# SSTuino_Evo.net
KiCad netlist of a schematic drawn in EAGLE
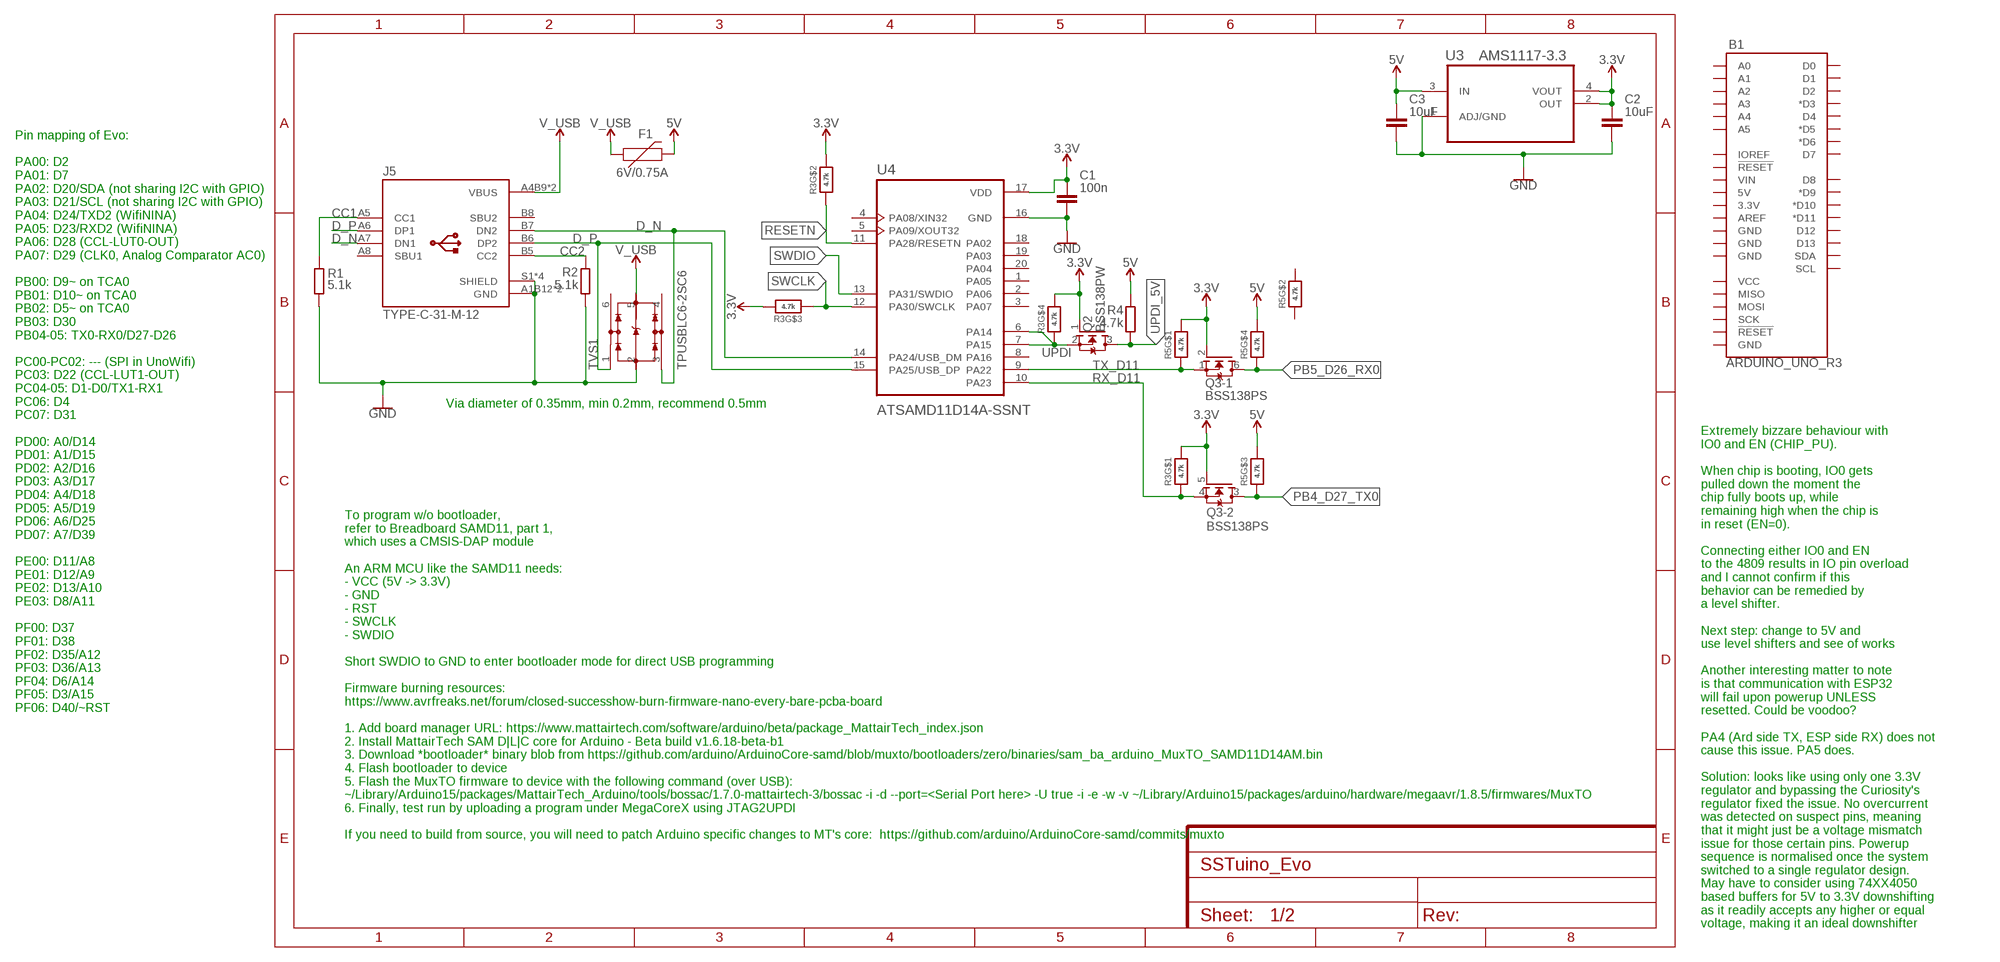
[diagram p0: schematic, sheet 1]
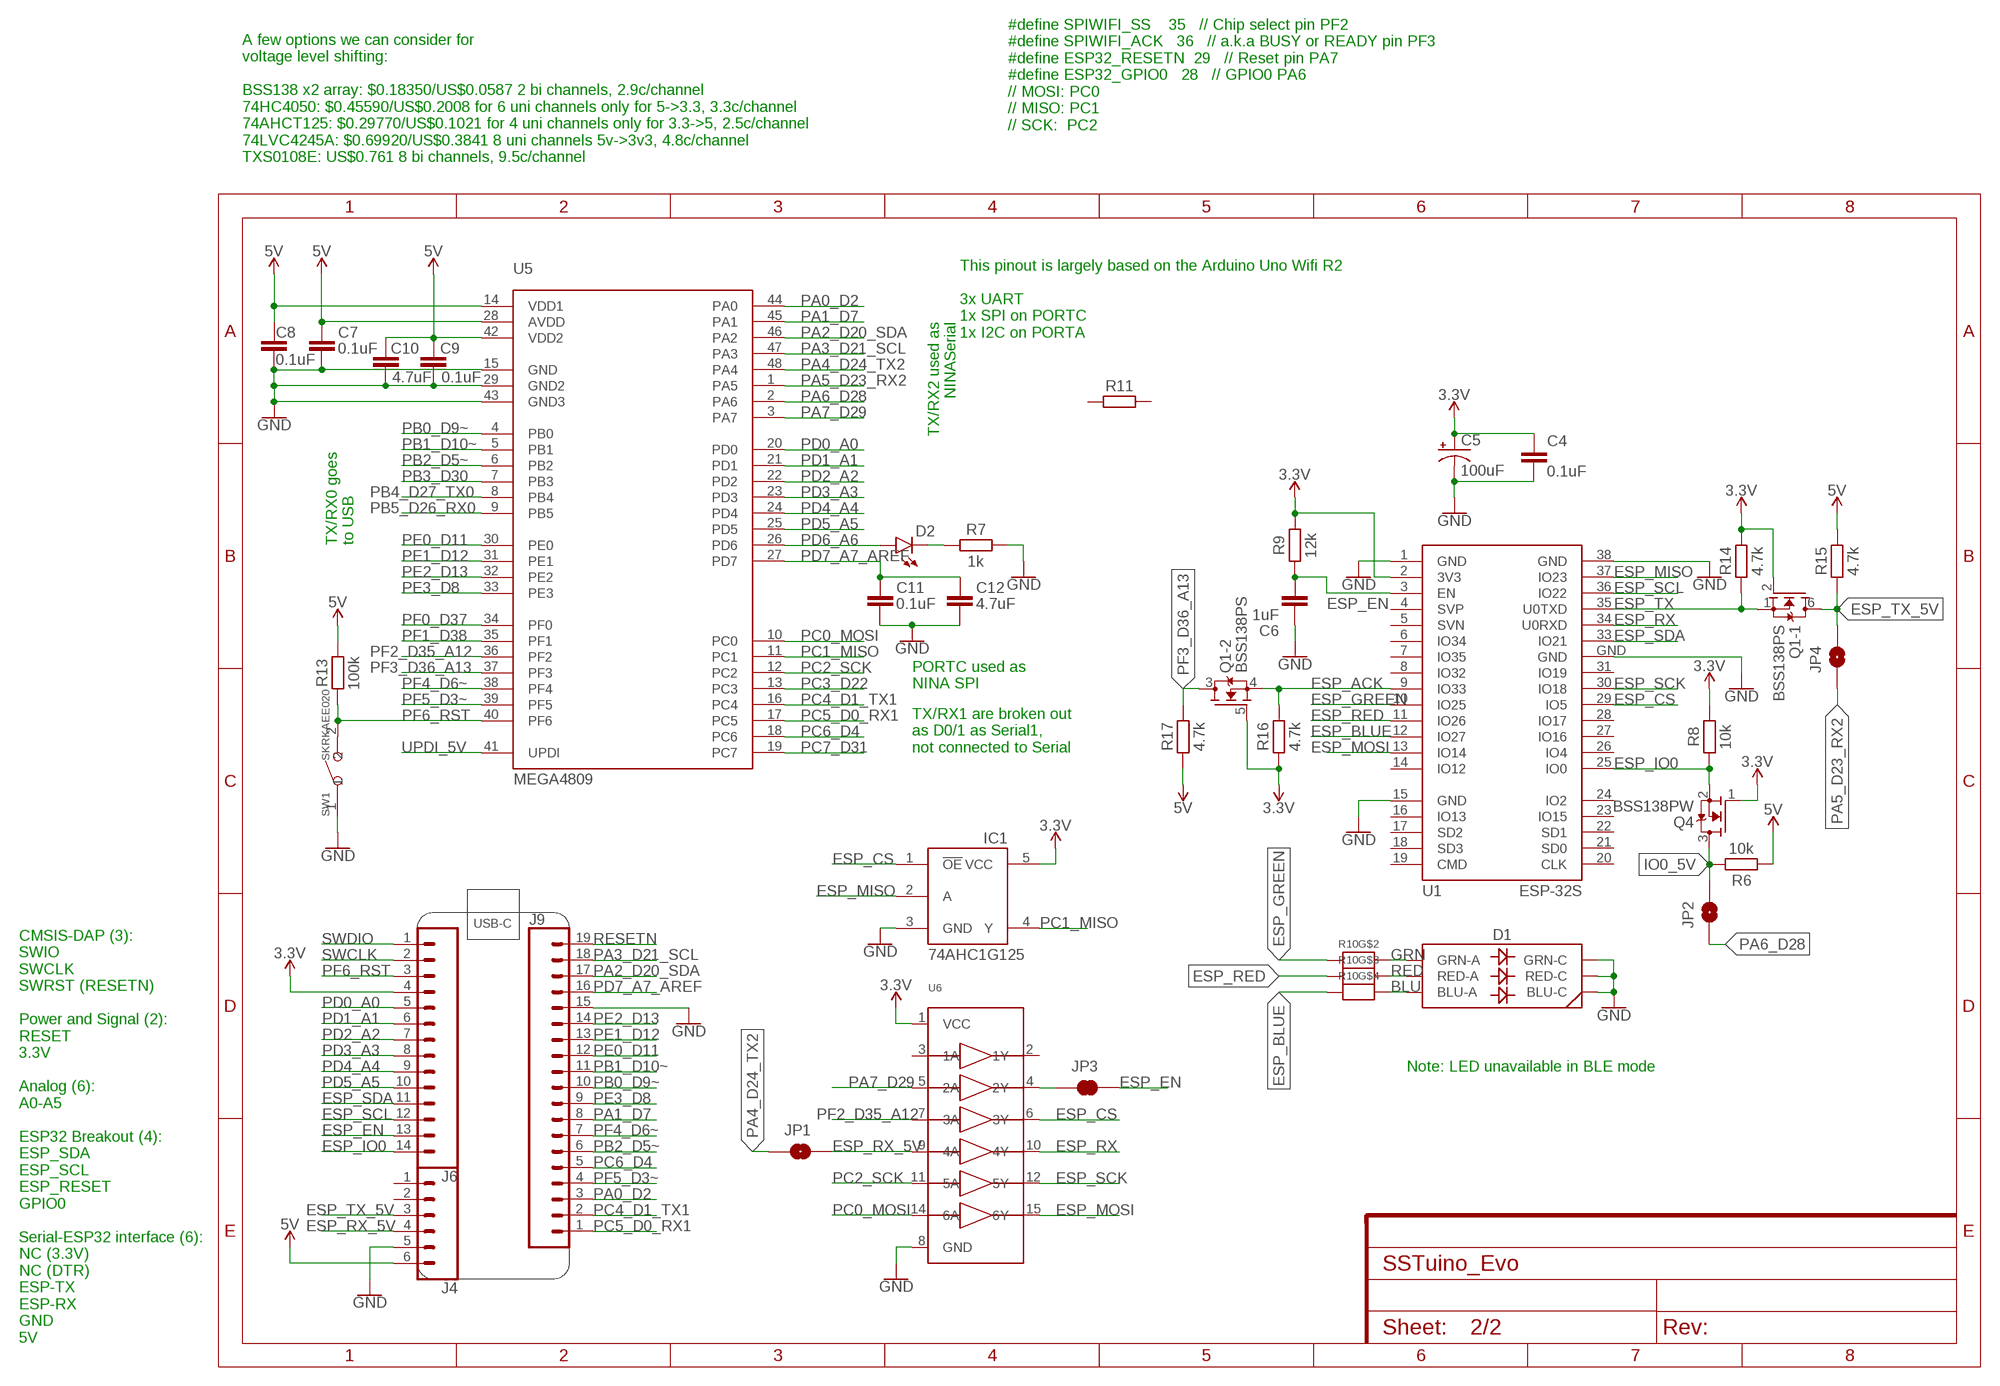
[diagram p1: schematic, sheet 2]

(export (version "E")
  (design (tool "Eeschema 10.0.6"))
  (components
    (comp (ref "B1")
      (value "ARDUINO_UNO_R3")
      (footprint "eagle-import:ARDUINO_R3")
      (libsource (lib "eagle-import") (part "ARDUINO_UNO_R3"))
    )
    (comp (ref "C1")
      (value "100n")
      (footprint "eagle-import:CAPC1005X60")
      (libsource (lib "eagle-import") (part "CCHIP-0402(1005-METRIC)_"))
    )
    (comp (ref "C2")
      (value "10uF")
      (footprint "eagle-import:CAPC1608X85")
      (fields (field (name "LCSC_PART") "C19702"))
      (libsource (lib "eagle-import") (part "CCHIP-0603(1608-METRIC)_"))
    )
    (comp (ref "C3")
      (value "10uF")
      (footprint "eagle-import:CAPC1608X85")
      (fields (field (name "LCSC_PART") "C19702"))
      (libsource (lib "eagle-import") (part "CCHIP-0603(1608-METRIC)_"))
    )
    (comp (ref "F1")
      (value "6V/0.75A")
      (footprint "eagle-import:1206")
      (fields (field (name "LCSC_PART") "C99563"))
      (libsource (lib "eagle-import") (part "PPTC_THREE-QUARTER-AMP"))
    )
    (comp (ref "J5")
      (value "TYPE-C-31-M-12")
      (footprint "eagle-import:HRO_TYPE-C-31-M-12")
      (fields (field (name "MF") "HRO Electronics Co., Ltd.") (field (name "LCSC_PART") "C165948"))
      (libsource (lib "eagle-import") (part "TYPE-C-31-M-12"))
    )
    (comp (ref "Q2")
      (value "BSS138PW")
      (footprint "eagle-import:SOT65P210X110-3N")
      (fields (field (name "MF") "NXP Semiconductors"))
      (libsource (lib "eagle-import") (part "BSS138PW"))
    )
    (comp (ref "Q3")
      (value "BSS138PS")
      (footprint "eagle-import:ARDUINO-TRANSISTORS_SOT363")
      (fields (field (name "MANUFACTURER") "NXP") (field (name "LCSC_PART") "C193381"))
      (libsource (lib "eagle-import") (part "BSS138PS"))
    )
    (comp (ref "R1")
      (value "5.1k")
      (footprint "eagle-import:RESC1005X40")
      (libsource (lib "eagle-import") (part "RCHIP-0402(1005-METRIC)_"))
    )
    (comp (ref "R2")
      (value "5.1k")
      (footprint "eagle-import:RESC1005X40")
      (libsource (lib "eagle-import") (part "RCHIP-0402(1005-METRIC)_"))
    )
    (comp (ref "R3")
      (value "4.7k")
      (footprint "eagle-import:RESPACK_4X0402")
      (fields (field (name "LCSC_PART") "C1980"))
      (libsource (lib "eagle-import") (part "RESISTOR_4PACK0402"))
    )
    (comp (ref "R4")
      (value "4.7k")
      (footprint "eagle-import:RESC1005X40")
      (libsource (lib "eagle-import") (part "RCHIP-0402(1005-METRIC)_"))
    )
    (comp (ref "R5")
      (value "4.7k")
      (footprint "eagle-import:RESPACK_4X0402")
      (fields (field (name "LCSC_PART") "C1980"))
      (libsource (lib "eagle-import") (part "RESISTOR_4PACK0402"))
    )
    (comp (ref "TVS1")
      (value "TPUSBLC6-2SC6")
      (footprint "eagle-import:SOT95P280X110-6N")
      (fields (field (name "LCSC_PART") "C558442"))
      (libsource (lib "eagle-import") (part "TPUSBLC6-2SC6"))
    )
    (comp (ref "U3")
      (value "AMS1117-3.3")
      (footprint "eagle-import:SOT230P696X180-4N")
      (fields (field (name "MPN") "LM1117MP-3.3") (field (name "LCSC_PART") "C6186"))
      (libsource (lib "eagle-import") (part "LM1117MP-3.3"))
    )
    (comp (ref "U4")
      (value "ATSAMD11D14A-SSNT")
      (footprint "eagle-import:SOIC127P1030X265-20N")
      (fields (field (name "MF") "Microchip") (field (name "LCSC_PART") "C2053599"))
      (libsource (lib "eagle-import") (part "ATSAMD11D14A-SSNT"))
    )
    (comp (ref "C4")
      (value "0.1uF")
      (footprint "eagle-import:CAPC1005X60")
      (libsource (lib "eagle-import") (part "CCHIP-0402(1005-METRIC)_"))
    )
    (comp (ref "C5")
      (value "100uF")
      (footprint "eagle-import:CAPMP3216X180N")
      (libsource (lib "eagle-import") (part "C-POL-USTANTALUM-1206(3216-METRIC)_"))
    )
    (comp (ref "C6")
      (value "1uF")
      (footprint "eagle-import:CAPC1005X60")
      (libsource (lib "eagle-import") (part "CCHIP-0402(1005-METRIC)_"))
    )
    (comp (ref "C7")
      (value "0.1uF")
      (footprint "eagle-import:CAPC1005X60")
      (libsource (lib "eagle-import") (part "CCHIP-0402(1005-METRIC)_"))
    )
    (comp (ref "C8")
      (value "0.1uF")
      (footprint "eagle-import:CAPC1005X60")
      (libsource (lib "eagle-import") (part "CCHIP-0402(1005-METRIC)_"))
    )
    (comp (ref "C9")
      (value "0.1uF")
      (footprint "eagle-import:CAPC1005X60")
      (libsource (lib "eagle-import") (part "CCHIP-0402(1005-METRIC)_"))
    )
    (comp (ref "C10")
      (value "4.7uF")
      (footprint "eagle-import:CAPC1005X60")
      (libsource (lib "eagle-import") (part "CCHIP-0402(1005-METRIC)_"))
    )
    (comp (ref "C11")
      (value "0.1uF")
      (footprint "eagle-import:CAPC1005X60")
      (libsource (lib "eagle-import") (part "CCHIP-0402(1005-METRIC)_"))
    )
    (comp (ref "C12")
      (value "4.7uF")
      (footprint "eagle-import:CAPC1005X60")
      (libsource (lib "eagle-import") (part "CCHIP-0402(1005-METRIC)_"))
    )
    (comp (ref "D1")
      (value "LED-RGBTC5050RGBF08")
      (footprint "eagle-import:LED-TRICOLOR-5050")
      (libsource (lib "eagle-import") (part "LED-RGBTC5050RGBF08"))
    )
    (comp (ref "D2")
      (value "LED0603")
      (footprint "eagle-import:LED-0603")
      (libsource (lib "eagle-import") (part "LED0603"))
    )
    (comp (ref "IC1")
      (value "74AHC1G125")
      (footprint "eagle-import:SOT23-5L")
      (fields (field (name "LCSC_PART") "C124295"))
      (libsource (lib "eagle-import") (part "74AHC1G125"))
    )
    (comp (ref "J4")
      (value "CONN_06NO_SILK_FEMALE_PTH")
      (footprint "eagle-import:1X06_NO_SILK")
      (libsource (lib "eagle-import") (part "CONN_06NO_SILK_FEMALE_PTH"))
    )
    (comp (ref "J6")
      (value "CONN_14NO_SILK")
      (footprint "eagle-import:1X14_NO_SILK")
      (libsource (lib "eagle-import") (part "CONN_14NO_SILK"))
    )
    (comp (ref "J9")
      (value "CONN_191X19_NO_SILK")
      (footprint "eagle-import:1X19_NO_SILK")
      (libsource (lib "eagle-import") (part "CONN_191X19_NO_SILK"))
    )
    (comp (ref "JP1")
      (value "JUMPER-SMT_2_NO_SILK")
      (footprint "eagle-import:SMT-JUMPER_2_NO_SILK")
      (libsource (lib "eagle-import") (part "JUMPER-SMT_2_NO_SILK"))
    )
    (comp (ref "JP2")
      (value "JUMPER-SMT_2_NO_SILK")
      (footprint "eagle-import:SMT-JUMPER_2_NO_SILK")
      (libsource (lib "eagle-import") (part "JUMPER-SMT_2_NO_SILK"))
    )
    (comp (ref "JP3")
      (value "JUMPER-SMT_2_NC_TRACE_SILK")
      (footprint "eagle-import:SMT-JUMPER_2_NC_TRACE_SILK")
      (libsource (lib "eagle-import") (part "JUMPER-SMT_2_NC_TRACE_SILK"))
    )
    (comp (ref "JP4")
      (value "JUMPER-SMT_2_NO_SILK")
      (footprint "eagle-import:SMT-JUMPER_2_NO_SILK")
      (libsource (lib "eagle-import") (part "JUMPER-SMT_2_NO_SILK"))
    )
    (comp (ref "Q1")
      (value "BSS138PS")
      (footprint "eagle-import:ARDUINO-TRANSISTORS_SOT363")
      (fields (field (name "MANUFACTURER") "NXP") (field (name "LCSC_PART") "C193381"))
      (libsource (lib "eagle-import") (part "BSS138PS"))
    )
    (comp (ref "Q4")
      (value "BSS138PW")
      (footprint "eagle-import:SOT65P210X110-3N")
      (fields (field (name "MF") "NXP Semiconductors"))
      (libsource (lib "eagle-import") (part "BSS138PW"))
    )
    (comp (ref "R6")
      (value "10k")
      (footprint "eagle-import:RESC1005X40")
      (libsource (lib "eagle-import") (part "RCHIP-0402(1005-METRIC)_"))
    )
    (comp (ref "R7")
      (value "1k")
      (footprint "eagle-import:RESC1005X40")
      (libsource (lib "eagle-import") (part "RCHIP-0402(1005-METRIC)_"))
    )
    (comp (ref "R8")
      (value "10k")
      (footprint "eagle-import:RESC1005X40")
      (libsource (lib "eagle-import") (part "RCHIP-0402(1005-METRIC)_"))
    )
    (comp (ref "R9")
      (value "12k")
      (footprint "eagle-import:RESC1005X40")
      (libsource (lib "eagle-import") (part "RCHIP-0402(1005-METRIC)_"))
    )
    (comp (ref "R10")
      (value "RESISTOR_4PACK0402")
      (footprint "eagle-import:RESPACK_4X0402")
      (libsource (lib "eagle-import") (part "RESISTOR_4PACK0402"))
    )
    (comp (ref "R11")
      (value "R_CHIP-0603(1608-METRIC)")
      (footprint "eagle-import:RESC1608X60")
      (libsource (lib "eagle-import") (part "RCHIP-0603(1608-METRIC)_"))
    )
    (comp (ref "R13")
      (value "100k")
      (footprint "eagle-import:RESC1005X40")
      (libsource (lib "eagle-import") (part "RCHIP-0402(1005-METRIC)_"))
    )
    (comp (ref "R14")
      (value "4.7k")
      (footprint "eagle-import:RESC1005X40")
      (libsource (lib "eagle-import") (part "RCHIP-0402(1005-METRIC)_"))
    )
    (comp (ref "R15")
      (value "4.7k")
      (footprint "eagle-import:RESC1005X40")
      (libsource (lib "eagle-import") (part "RCHIP-0402(1005-METRIC)_"))
    )
    (comp (ref "R16")
      (value "4.7k")
      (footprint "eagle-import:RESC1005X40")
      (libsource (lib "eagle-import") (part "RCHIP-0402(1005-METRIC)_"))
    )
    (comp (ref "R17")
      (value "4.7k")
      (footprint "eagle-import:RESC1005X40")
      (libsource (lib "eagle-import") (part "RCHIP-0402(1005-METRIC)_"))
    )
    (comp (ref "SW1")
      (value "SKRKAEE020")
      (footprint "eagle-import:SW2-2.6-3.9X2.9X1.5+0.4MM")
      (fields (field (name "LCSC_PART") "C115357") (field (name "LCSC_PART_1") "C115357"))
      (libsource (lib "eagle-import") (part "SMD-BUTTON(2P-3.9X2.9X1.5+0.4MM)-SKRKAEE020"))
    )
    (comp (ref "U1")
      (value "ESP-32S")
      (footprint "eagle-import:ESP-32S")
      (libsource (lib "eagle-import") (part "ESP-32S"))
    )
    (comp (ref "U5")
      (value "MEGA4809")
      (footprint "eagle-import:TQFP48")
      (fields (field (name "LCSC_PART") "C189475"))
      (libsource (lib "eagle-import") (part "MEGA4809"))
    )
    (comp (ref "U6")
      (value "74HC4050DTSSOP")
      (footprint "eagle-import:TSSOP16")
      (fields (field (name "LCSC_PART") "C352825"))
      (libsource (lib "eagle-import") (part "74HC4050DTSSOP"))
    )
  )
  (nets
    (net (code "1") (name "3.3V") (class "Default")
      (node (ref "C1") (pin "1") (pinfunction "1_1") (pintype "passive"))
      (node (ref "C2") (pin "1") (pinfunction "1_1") (pintype "passive"))
      (node (ref "C4") (pin "1") (pinfunction "1_1") (pintype "passive"))
      (node (ref "C5") (pin "1") (pinfunction "+_1") (pintype "passive"))
      (node (ref "IC1") (pin "5") (pinfunction "VCC_5") (pintype "power_in"))
      (node (ref "J6") (pin "4") (pinfunction "4_4") (pintype "passive"))
      (node (ref "Q1") (pin "2") (pinfunction "G_2") (pintype "passive"))
      (node (ref "Q1") (pin "5") (pinfunction "G_5") (pintype "passive"))
      (node (ref "Q2") (pin "1") (pinfunction "G_1") (pintype "passive"))
      (node (ref "Q3") (pin "2") (pinfunction "G_2") (pintype "passive"))
      (node (ref "Q3") (pin "5") (pinfunction "G_5") (pintype "passive"))
      (node (ref "Q4") (pin "1") (pinfunction "G_1") (pintype "passive"))
      (node (ref "R14") (pin "2") (pinfunction "2_2") (pintype "passive"))
      (node (ref "R16") (pin "1") (pinfunction "1_1") (pintype "passive"))
      (node (ref "R3") (pin "5") (pinfunction "2_5") (pintype "passive"))
      (node (ref "R3") (pin "6") (pinfunction "2_6") (pintype "passive"))
      (node (ref "R3") (pin "7") (pinfunction "2_7") (pintype "passive"))
      (node (ref "R3") (pin "8") (pinfunction "2_8") (pintype "passive"))
      (node (ref "R5") (pin "8") (pinfunction "2_8") (pintype "passive"))
      (node (ref "R8") (pin "2") (pinfunction "2_2") (pintype "passive"))
      (node (ref "R9") (pin "2") (pinfunction "2_2") (pintype "passive"))
      (node (ref "U1") (pin "2") (pinfunction "3V3_2") (pintype "power_in"))
      (node (ref "U3") (pin "2") (pinfunction "OUT_2") (pintype "output"))
      (node (ref "U3") (pin "4") (pinfunction "VOUT_4") (pintype "output"))
      (node (ref "U4") (pin "17") (pinfunction "VDD_17") (pintype "power_in"))
      (node (ref "U6") (pin "1") (pinfunction "VCC_1") (pintype "bidirectional"))
    )
    (net (code "2") (name "5V") (class "Default")
      (node (ref "C10") (pin "1") (pinfunction "1_1") (pintype "passive"))
      (node (ref "C3") (pin "1") (pinfunction "1_1") (pintype "passive"))
      (node (ref "C7") (pin "1") (pinfunction "1_1") (pintype "passive"))
      (node (ref "C8") (pin "1") (pinfunction "1_1") (pintype "passive"))
      (node (ref "C9") (pin "1") (pinfunction "1_1") (pintype "passive"))
      (node (ref "F1") (pin "2") (pinfunction "2_2") (pintype "bidirectional"))
      (node (ref "J4") (pin "6") (pinfunction "6_6") (pintype "passive"))
      (node (ref "R13") (pin "2") (pinfunction "2_2") (pintype "passive"))
      (node (ref "R15") (pin "2") (pinfunction "2_2") (pintype "passive"))
      (node (ref "R17") (pin "1") (pinfunction "1_1") (pintype "passive"))
      (node (ref "R4") (pin "2") (pinfunction "2_2") (pintype "passive"))
      (node (ref "R5") (pin "5") (pinfunction "2_5") (pintype "passive"))
      (node (ref "R5") (pin "6") (pinfunction "2_6") (pintype "passive"))
      (node (ref "R6") (pin "1") (pinfunction "1_1") (pintype "passive"))
      (node (ref "U3") (pin "3") (pinfunction "IN_3") (pintype "input"))
      (node (ref "U5") (pin "14") (pinfunction "VDD1_14") (pintype "bidirectional"))
      (node (ref "U5") (pin "28") (pinfunction "AVDD_28") (pintype "bidirectional"))
      (node (ref "U5") (pin "42") (pinfunction "VDD2_42") (pintype "bidirectional"))
    )
    (net (code "3") (name "BLU") (class "Default")
      (node (ref "D1") (pin "6") (pinfunction "BLU-A_6") (pintype "bidirectional"))
      (node (ref "R10") (pin "5") (pinfunction "2_5") (pintype "passive"))
    )
    (net (code "4") (name "CC1") (class "Default")
      (node (ref "J5") (pin "A5") (pinfunction "CC1_A5") (pintype "bidirectional"))
      (node (ref "R1") (pin "1") (pinfunction "1_1") (pintype "passive"))
    )
    (net (code "5") (name "CC2") (class "Default")
      (node (ref "J5") (pin "B5") (pinfunction "CC2_B5") (pintype "bidirectional"))
      (node (ref "R2") (pin "2") (pinfunction "2_2") (pintype "passive"))
    )
    (net (code "6") (name "D_N") (class "Default")
      (node (ref "J5") (pin "A7") (pinfunction "DN1_A7") (pintype "bidirectional"))
      (node (ref "J5") (pin "B7") (pinfunction "DN2_B7") (pintype "bidirectional"))
      (node (ref "TVS1") (pin "3") (pinfunction "IO2_3") (pintype "passive"))
      (node (ref "U4") (pin "14") (pinfunction "PA24/USB_DM_14") (pintype "bidirectional"))
    )
    (net (code "7") (name "D_P") (class "Default")
      (node (ref "J5") (pin "A6") (pinfunction "DP1_A6") (pintype "bidirectional"))
      (node (ref "J5") (pin "B6") (pinfunction "DP2_B6") (pintype "bidirectional"))
      (node (ref "TVS1") (pin "1") (pinfunction "IO1_1") (pintype "passive"))
      (node (ref "U4") (pin "15") (pinfunction "PA25/USB_DP_15") (pintype "bidirectional"))
    )
    (net (code "8") (name "ESP_ACK") (class "Default")
      (node (ref "Q1") (pin "4") (pinfunction "S_4") (pintype "passive"))
      (node (ref "R16") (pin "2") (pinfunction "2_2") (pintype "passive"))
      (node (ref "U1") (pin "9") (pinfunction "IO33_9") (pintype "bidirectional"))
    )
    (net (code "9") (name "ESP_BLUE") (class "Default")
      (node (ref "R10") (pin "4") (pinfunction "1_4") (pintype "passive"))
      (node (ref "U1") (pin "12") (pinfunction "IO27_12") (pintype "bidirectional"))
    )
    (net (code "10") (name "ESP_CS") (class "Default")
      (node (ref "IC1") (pin "1") (pinfunction "~{OE}_1") (pintype "input"))
      (node (ref "U1") (pin "29") (pinfunction "IO5_29") (pintype "bidirectional"))
      (node (ref "U6") (pin "6") (pinfunction "3Y_6") (pintype "bidirectional"))
    )
    (net (code "11") (name "ESP_EN") (class "Default")
      (node (ref "C6") (pin "2") (pinfunction "2_2") (pintype "passive"))
      (node (ref "J6") (pin "13") (pinfunction "13_13") (pintype "passive"))
      (node (ref "JP3") (pin "2") (pinfunction "2_2") (pintype "passive"))
      (node (ref "R9") (pin "1") (pinfunction "1_1") (pintype "passive"))
      (node (ref "U1") (pin "3") (pinfunction "EN_3") (pintype "input"))
    )
    (net (code "12") (name "ESP_GREEN") (class "Default")
      (node (ref "R10") (pin "2") (pinfunction "1_2") (pintype "passive"))
      (node (ref "U1") (pin "10") (pinfunction "IO25_10") (pintype "bidirectional"))
    )
    (net (code "13") (name "ESP_IO0") (class "Default")
      (node (ref "J6") (pin "14") (pinfunction "14_14") (pintype "passive"))
      (node (ref "Q4") (pin "2") (pinfunction "S_2") (pintype "passive"))
      (node (ref "R8") (pin "1") (pinfunction "1_1") (pintype "passive"))
      (node (ref "U1") (pin "25") (pinfunction "IO0_25") (pintype "bidirectional"))
    )
    (net (code "14") (name "ESP_MISO") (class "Default")
      (node (ref "IC1") (pin "2") (pinfunction "A_2") (pintype "input"))
      (node (ref "U1") (pin "37") (pinfunction "IO23_37") (pintype "bidirectional"))
    )
    (net (code "15") (name "ESP_MOSI") (class "Default")
      (node (ref "U1") (pin "13") (pinfunction "IO14_13") (pintype "bidirectional"))
      (node (ref "U6") (pin "15") (pinfunction "6Y_15") (pintype "bidirectional"))
    )
    (net (code "16") (name "ESP_RED") (class "Default")
      (node (ref "R10") (pin "3") (pinfunction "1_3") (pintype "passive"))
      (node (ref "U1") (pin "11") (pinfunction "IO26_11") (pintype "bidirectional"))
    )
    (net (code "17") (name "ESP_RX") (class "Default")
      (node (ref "U1") (pin "34") (pinfunction "U0RXD_34") (pintype "bidirectional"))
      (node (ref "U6") (pin "10") (pinfunction "4Y_10") (pintype "bidirectional"))
    )
    (net (code "18") (name "ESP_RX_5V") (class "Default")
      (node (ref "J4") (pin "4") (pinfunction "4_4") (pintype "passive"))
      (node (ref "JP1") (pin "2") (pinfunction "2_2") (pintype "passive"))
      (node (ref "U6") (pin "9") (pinfunction "4A_9") (pintype "bidirectional"))
    )
    (net (code "19") (name "ESP_SCK") (class "Default")
      (node (ref "U1") (pin "30") (pinfunction "IO18_30") (pintype "bidirectional"))
      (node (ref "U6") (pin "12") (pinfunction "5Y_12") (pintype "bidirectional"))
    )
    (net (code "20") (name "ESP_SCL") (class "Default")
      (node (ref "J6") (pin "12") (pinfunction "12_12") (pintype "passive"))
      (node (ref "U1") (pin "36") (pinfunction "IO22_36") (pintype "bidirectional"))
    )
    (net (code "21") (name "ESP_SDA") (class "Default")
      (node (ref "J6") (pin "11") (pinfunction "11_11") (pintype "passive"))
      (node (ref "U1") (pin "33") (pinfunction "IO21_33") (pintype "bidirectional"))
    )
    (net (code "22") (name "ESP_TX") (class "Default")
      (node (ref "Q1") (pin "1") (pinfunction "S_1") (pintype "passive"))
      (node (ref "R14") (pin "1") (pinfunction "1_1") (pintype "passive"))
      (node (ref "U1") (pin "35") (pinfunction "U0TXD_35") (pintype "bidirectional"))
    )
    (net (code "23") (name "ESP_TX_5V") (class "Default")
      (node (ref "J4") (pin "3") (pinfunction "3_3") (pintype "passive"))
      (node (ref "JP4") (pin "2") (pinfunction "2_2") (pintype "passive"))
      (node (ref "Q1") (pin "6") (pinfunction "D_6") (pintype "passive"))
      (node (ref "R15") (pin "1") (pinfunction "1_1") (pintype "passive"))
    )
    (net (code "24") (name "GND") (class "Default")
      (node (ref "C1") (pin "2") (pinfunction "2_2") (pintype "passive"))
      (node (ref "C10") (pin "2") (pinfunction "2_2") (pintype "passive"))
      (node (ref "C11") (pin "2") (pinfunction "2_2") (pintype "passive"))
      (node (ref "C12") (pin "2") (pinfunction "2_2") (pintype "passive"))
      (node (ref "C2") (pin "2") (pinfunction "2_2") (pintype "passive"))
      (node (ref "C3") (pin "2") (pinfunction "2_2") (pintype "passive"))
      (node (ref "C4") (pin "2") (pinfunction "2_2") (pintype "passive"))
      (node (ref "C5") (pin "2") (pinfunction "-_2") (pintype "passive"))
      (node (ref "C6") (pin "1") (pinfunction "1_1") (pintype "passive"))
      (node (ref "C7") (pin "2") (pinfunction "2_2") (pintype "passive"))
      (node (ref "C8") (pin "2") (pinfunction "2_2") (pintype "passive"))
      (node (ref "C9") (pin "2") (pinfunction "2_2") (pintype "passive"))
      (node (ref "D1") (pin "1") (pinfunction "BLU-C_1") (pintype "bidirectional"))
      (node (ref "D1") (pin "2") (pinfunction "RED-C_2") (pintype "bidirectional"))
      (node (ref "D1") (pin "3") (pinfunction "GRN-C_3") (pintype "bidirectional"))
      (node (ref "IC1") (pin "3") (pinfunction "GND_3") (pintype "power_in"))
      (node (ref "J4") (pin "5") (pinfunction "5_5") (pintype "passive"))
      (node (ref "J5") (pin "A1B12") (pinfunction "GND_A1B12") (pintype "power_in"))
      (node (ref "J5") (pin "B1A12") (pinfunction "GND_B1A12") (pintype "power_in"))
      (node (ref "J5") (pin "S1") (pinfunction "SHIELD_S1") (pintype "passive"))
      (node (ref "J5") (pin "S2") (pinfunction "SHIELD_S2") (pintype "passive"))
      (node (ref "J5") (pin "S3") (pinfunction "SHIELD_S3") (pintype "passive"))
      (node (ref "J5") (pin "S4") (pinfunction "SHIELD_S4") (pintype "passive"))
      (node (ref "J9") (pin "15") (pinfunction "15_15") (pintype "passive"))
      (node (ref "R1") (pin "2") (pinfunction "2_2") (pintype "passive"))
      (node (ref "R2") (pin "1") (pinfunction "1_1") (pintype "passive"))
      (node (ref "R7") (pin "2") (pinfunction "2_2") (pintype "passive"))
      (node (ref "SW1") (pin "1") (pinfunction "1_1") (pintype "bidirectional"))
      (node (ref "TVS1") (pin "2") (pinfunction "VSS_2") (pintype "power_in"))
      (node (ref "U1") (pin "1") (pinfunction "GND_1") (pintype "power_in"))
      (node (ref "U1") (pin "15") (pinfunction "GND_15") (pintype "power_in"))
      (node (ref "U1") (pin "38") (pinfunction "GND_38") (pintype "power_in"))
      (node (ref "U1") (pin "GND") (pinfunction "GND_GND") (pintype "power_in"))
      (node (ref "U3") (pin "1") (pinfunction "ADJ/GND_1") (pintype "passive"))
      (node (ref "U4") (pin "16") (pinfunction "GND_16") (pintype "power_in"))
      (node (ref "U5") (pin "15") (pinfunction "GND_15") (pintype "bidirectional"))
      (node (ref "U5") (pin "29") (pinfunction "GND2_29") (pintype "bidirectional"))
      (node (ref "U5") (pin "43") (pinfunction "GND3_43") (pintype "bidirectional"))
      (node (ref "U6") (pin "8") (pinfunction "GND_8") (pintype "bidirectional"))
    )
    (net (code "25") (name "GRN") (class "Default")
      (node (ref "D1") (pin "4") (pinfunction "GRN-A_4") (pintype "bidirectional"))
      (node (ref "R10") (pin "7") (pinfunction "2_7") (pintype "passive"))
    )
    (net (code "26") (name "IO0_5V") (class "Default")
      (node (ref "JP2") (pin "2") (pinfunction "2_2") (pintype "passive"))
      (node (ref "Q4") (pin "3") (pinfunction "D_3") (pintype "passive"))
      (node (ref "R6") (pin "2") (pinfunction "2_2") (pintype "passive"))
    )
    (net (code "27") (name "Net-(D2-PadC)") (class "Default")
      (node (ref "D2") (pin "C") (pinfunction "C_C") (pintype "passive"))
      (node (ref "R7") (pin "1") (pinfunction "1_1") (pintype "passive"))
    )
    (net (code "28") (name "Net-(U6-2Y)") (class "Default")
      (node (ref "JP3") (pin "1") (pinfunction "1_1") (pintype "passive"))
      (node (ref "U6") (pin "4") (pinfunction "2Y_4") (pintype "bidirectional"))
    )
    (net (code "29") (name "PA0_D2") (class "Default")
      (node (ref "J9") (pin "3") (pinfunction "3_3") (pintype "passive"))
      (node (ref "U5") (pin "44") (pinfunction "PA0_44") (pintype "bidirectional"))
    )
    (net (code "30") (name "PA1_D7") (class "Default")
      (node (ref "J9") (pin "8") (pinfunction "8_8") (pintype "passive"))
      (node (ref "U5") (pin "45") (pinfunction "PA1_45") (pintype "bidirectional"))
    )
    (net (code "31") (name "PA2_D20_SDA") (class "Default")
      (node (ref "J9") (pin "17") (pinfunction "17_17") (pintype "passive"))
      (node (ref "U5") (pin "46") (pinfunction "PA2_46") (pintype "bidirectional"))
    )
    (net (code "32") (name "PA3_D21_SCL") (class "Default")
      (node (ref "J9") (pin "18") (pinfunction "18_18") (pintype "passive"))
      (node (ref "U5") (pin "47") (pinfunction "PA3_47") (pintype "bidirectional"))
    )
    (net (code "33") (name "PA4_D24_TX2") (class "Default")
      (node (ref "JP1") (pin "1") (pinfunction "1_1") (pintype "passive"))
      (node (ref "U5") (pin "48") (pinfunction "PA4_48") (pintype "bidirectional"))
    )
    (net (code "34") (name "PA5_D23_RX2") (class "Default")
      (node (ref "JP4") (pin "1") (pinfunction "1_1") (pintype "passive"))
      (node (ref "U5") (pin "1") (pinfunction "PA5_1") (pintype "bidirectional"))
    )
    (net (code "35") (name "PA6_D28") (class "Default")
      (node (ref "JP2") (pin "1") (pinfunction "1_1") (pintype "passive"))
      (node (ref "U5") (pin "2") (pinfunction "PA6_2") (pintype "bidirectional"))
    )
    (net (code "36") (name "PA7_D29") (class "Default")
      (node (ref "U5") (pin "3") (pinfunction "PA7_3") (pintype "bidirectional"))
      (node (ref "U6") (pin "5") (pinfunction "2A_5") (pintype "bidirectional"))
    )
    (net (code "37") (name "PB0_D9~{}") (class "Default")
      (node (ref "J9") (pin "10") (pinfunction "10_10") (pintype "passive"))
      (node (ref "U5") (pin "4") (pinfunction "PB0_4") (pintype "bidirectional"))
    )
    (net (code "38") (name "PB1_D10~{}") (class "Default")
      (node (ref "J9") (pin "11") (pinfunction "11_11") (pintype "passive"))
      (node (ref "U5") (pin "5") (pinfunction "PB1_5") (pintype "bidirectional"))
    )
    (net (code "39") (name "PB2_D5~{}") (class "Default")
      (node (ref "J9") (pin "6") (pinfunction "6_6") (pintype "passive"))
      (node (ref "U5") (pin "6") (pinfunction "PB2_6") (pintype "bidirectional"))
    )
    (net (code "40") (name "PB3_D30") (class "Default")
      (node (ref "U5") (pin "7") (pinfunction "PB3_7") (pintype "bidirectional"))
    )
    (net (code "41") (name "PB4_D27_TX0") (class "Default")
      (node (ref "Q3") (pin "3") (pinfunction "D_3") (pintype "passive"))
      (node (ref "R5") (pin "3") (pinfunction "1_3") (pintype "passive"))
      (node (ref "U5") (pin "8") (pinfunction "PB4_8") (pintype "bidirectional"))
    )
    (net (code "42") (name "PB5_D26_RX0") (class "Default")
      (node (ref "Q3") (pin "6") (pinfunction "D_6") (pintype "passive"))
      (node (ref "R5") (pin "4") (pinfunction "1_4") (pintype "passive"))
      (node (ref "U5") (pin "9") (pinfunction "PB5_9") (pintype "bidirectional"))
    )
    (net (code "43") (name "PC0_MOSI") (class "Default")
      (node (ref "U5") (pin "10") (pinfunction "PC0_10") (pintype "bidirectional"))
      (node (ref "U6") (pin "14") (pinfunction "6A_14") (pintype "bidirectional"))
    )
    (net (code "44") (name "PC1_MISO") (class "Default")
      (node (ref "IC1") (pin "4") (pinfunction "Y_4") (pintype "output"))
      (node (ref "U5") (pin "11") (pinfunction "PC1_11") (pintype "bidirectional"))
    )
    (net (code "45") (name "PC2_SCK") (class "Default")
      (node (ref "U5") (pin "12") (pinfunction "PC2_12") (pintype "bidirectional"))
      (node (ref "U6") (pin "11") (pinfunction "5A_11") (pintype "bidirectional"))
    )
    (net (code "46") (name "PC3_D22") (class "Default")
      (node (ref "U5") (pin "13") (pinfunction "PC3_13") (pintype "bidirectional"))
    )
    (net (code "47") (name "PC4_D1_TX1") (class "Default")
      (node (ref "J9") (pin "2") (pinfunction "2_2") (pintype "passive"))
      (node (ref "U5") (pin "16") (pinfunction "PC4_16") (pintype "bidirectional"))
    )
    (net (code "48") (name "PC5_D0_RX1") (class "Default")
      (node (ref "J9") (pin "1") (pinfunction "1_1") (pintype "passive"))
      (node (ref "U5") (pin "17") (pinfunction "PC5_17") (pintype "bidirectional"))
    )
    (net (code "49") (name "PC6_D4") (class "Default")
      (node (ref "J9") (pin "5") (pinfunction "5_5") (pintype "passive"))
      (node (ref "U5") (pin "18") (pinfunction "PC6_18") (pintype "bidirectional"))
    )
    (net (code "50") (name "PC7_D31") (class "Default")
      (node (ref "U5") (pin "19") (pinfunction "PC7_19") (pintype "bidirectional"))
    )
    (net (code "51") (name "PD0_A0") (class "Default")
      (node (ref "J6") (pin "5") (pinfunction "5_5") (pintype "passive"))
      (node (ref "U5") (pin "20") (pinfunction "PD0_20") (pintype "bidirectional"))
    )
    (net (code "52") (name "PD1_A1") (class "Default")
      (node (ref "J6") (pin "6") (pinfunction "6_6") (pintype "passive"))
      (node (ref "U5") (pin "21") (pinfunction "PD1_21") (pintype "bidirectional"))
    )
    (net (code "53") (name "PD2_A2") (class "Default")
      (node (ref "J6") (pin "7") (pinfunction "7_7") (pintype "passive"))
      (node (ref "U5") (pin "22") (pinfunction "PD2_22") (pintype "bidirectional"))
    )
    (net (code "54") (name "PD3_A3") (class "Default")
      (node (ref "J6") (pin "8") (pinfunction "8_8") (pintype "passive"))
      (node (ref "U5") (pin "23") (pinfunction "PD3_23") (pintype "bidirectional"))
    )
    (net (code "55") (name "PD4_A4") (class "Default")
      (node (ref "J6") (pin "9") (pinfunction "9_9") (pintype "passive"))
      (node (ref "U5") (pin "24") (pinfunction "PD4_24") (pintype "bidirectional"))
    )
    (net (code "56") (name "PD5_A5") (class "Default")
      (node (ref "J6") (pin "10") (pinfunction "10_10") (pintype "passive"))
      (node (ref "U5") (pin "25") (pinfunction "PD5_25") (pintype "bidirectional"))
    )
    (net (code "57") (name "PD6_A6") (class "Default")
      (node (ref "D2") (pin "A") (pinfunction "A_A") (pintype "passive"))
      (node (ref "U5") (pin "26") (pinfunction "PD6_26") (pintype "bidirectional"))
    )
    (net (code "58") (name "PD7_A7_AREF") (class "Default")
      (node (ref "C11") (pin "1") (pinfunction "1_1") (pintype "passive"))
      (node (ref "C12") (pin "1") (pinfunction "1_1") (pintype "passive"))
      (node (ref "J9") (pin "16") (pinfunction "16_16") (pintype "passive"))
      (node (ref "U5") (pin "27") (pinfunction "PD7_27") (pintype "bidirectional"))
    )
    (net (code "59") (name "PE0_D11") (class "Default")
      (node (ref "J9") (pin "12") (pinfunction "12_12") (pintype "passive"))
      (node (ref "U5") (pin "30") (pinfunction "PE0_30") (pintype "bidirectional"))
    )
    (net (code "60") (name "PE1_D12") (class "Default")
      (node (ref "J9") (pin "13") (pinfunction "13_13") (pintype "passive"))
      (node (ref "U5") (pin "31") (pinfunction "PE1_31") (pintype "bidirectional"))
    )
    (net (code "61") (name "PE2_D13") (class "Default")
      (node (ref "J9") (pin "14") (pinfunction "14_14") (pintype "passive"))
      (node (ref "U5") (pin "32") (pinfunction "PE2_32") (pintype "bidirectional"))
    )
    (net (code "62") (name "PE3_D8") (class "Default")
      (node (ref "J9") (pin "9") (pinfunction "9_9") (pintype "passive"))
      (node (ref "U5") (pin "33") (pinfunction "PE3_33") (pintype "bidirectional"))
    )
    (net (code "63") (name "PF0_D37") (class "Default")
      (node (ref "U5") (pin "34") (pinfunction "PF0_34") (pintype "bidirectional"))
    )
    (net (code "64") (name "PF1_D38") (class "Default")
      (node (ref "U5") (pin "35") (pinfunction "PF1_35") (pintype "bidirectional"))
    )
    (net (code "65") (name "PF2_D35_A12") (class "Default")
      (node (ref "U5") (pin "36") (pinfunction "PF2_36") (pintype "bidirectional"))
      (node (ref "U6") (pin "7") (pinfunction "3A_7") (pintype "bidirectional"))
    )
    (net (code "66") (name "PF3_D36_A13") (class "Default")
      (node (ref "Q1") (pin "3") (pinfunction "D_3") (pintype "passive"))
      (node (ref "R17") (pin "2") (pinfunction "2_2") (pintype "passive"))
      (node (ref "U5") (pin "37") (pinfunction "PF3_37") (pintype "bidirectional"))
    )
    (net (code "67") (name "PF4_D6~{}") (class "Default")
      (node (ref "J9") (pin "7") (pinfunction "7_7") (pintype "passive"))
      (node (ref "U5") (pin "38") (pinfunction "PF4_38") (pintype "bidirectional"))
    )
    (net (code "68") (name "PF5_D3~{}") (class "Default")
      (node (ref "J9") (pin "4") (pinfunction "4_4") (pintype "passive"))
      (node (ref "U5") (pin "39") (pinfunction "PF5_39") (pintype "bidirectional"))
    )
    (net (code "69") (name "PF6_RST") (class "Default")
      (node (ref "J6") (pin "3") (pinfunction "3_3") (pintype "passive"))
      (node (ref "R13") (pin "1") (pinfunction "1_1") (pintype "passive"))
      (node (ref "SW1") (pin "2") (pinfunction "2_2") (pintype "bidirectional"))
      (node (ref "U5") (pin "40") (pinfunction "PF6_40") (pintype "bidirectional"))
    )
    (net (code "70") (name "RED") (class "Default")
      (node (ref "D1") (pin "5") (pinfunction "RED-A_5") (pintype "bidirectional"))
      (node (ref "R10") (pin "6") (pinfunction "2_6") (pintype "passive"))
    )
    (net (code "71") (name "RESETN") (class "Default")
      (node (ref "J9") (pin "19") (pinfunction "19_19") (pintype "passive"))
      (node (ref "R3") (pin "2") (pinfunction "1_2") (pintype "passive"))
      (node (ref "U4") (pin "11") (pinfunction "PA28/RESETN_11") (pintype "input"))
    )
    (net (code "72") (name "RX_D11") (class "Default")
      (node (ref "Q3") (pin "4") (pinfunction "S_4") (pintype "passive"))
      (node (ref "R3") (pin "1") (pinfunction "1_1") (pintype "passive"))
      (node (ref "U4") (pin "10") (pinfunction "PA23_10") (pintype "bidirectional"))
    )
    (net (code "73") (name "SWCLK") (class "Default")
      (node (ref "J6") (pin "2") (pinfunction "2_2") (pintype "passive"))
      (node (ref "R3") (pin "3") (pinfunction "1_3") (pintype "passive"))
      (node (ref "U4") (pin "12") (pinfunction "PA30/SWCLK_12") (pintype "bidirectional"))
    )
    (net (code "74") (name "SWDIO") (class "Default")
      (node (ref "J6") (pin "1") (pinfunction "1_1") (pintype "passive"))
      (node (ref "U4") (pin "13") (pinfunction "PA31/SWDIO_13") (pintype "bidirectional"))
    )
    (net (code "75") (name "TX_D11") (class "Default")
      (node (ref "Q3") (pin "1") (pinfunction "S_1") (pintype "passive"))
      (node (ref "R5") (pin "1") (pinfunction "1_1") (pintype "passive"))
      (node (ref "U4") (pin "9") (pinfunction "PA22_9") (pintype "bidirectional"))
    )
    (net (code "76") (name "UPDI") (class "Default")
      (node (ref "Q2") (pin "2") (pinfunction "S_2") (pintype "passive"))
      (node (ref "R3") (pin "4") (pinfunction "1_4") (pintype "passive"))
      (node (ref "U4") (pin "6") (pinfunction "PA14_6") (pintype "bidirectional"))
      (node (ref "U4") (pin "7") (pinfunction "PA15_7") (pintype "bidirectional"))
    )
    (net (code "77") (name "UPDI_5V") (class "Default")
      (node (ref "Q2") (pin "3") (pinfunction "D_3") (pintype "passive"))
      (node (ref "R4") (pin "1") (pinfunction "1_1") (pintype "passive"))
      (node (ref "U5") (pin "41") (pinfunction "UPDI_41") (pintype "bidirectional"))
    )
    (net (code "78") (name "V_USB") (class "Default")
      (node (ref "F1") (pin "1") (pinfunction "1_1") (pintype "bidirectional"))
      (node (ref "J5") (pin "A4B9") (pinfunction "VBUS_A4B9") (pintype "power_in"))
      (node (ref "J5") (pin "B4A9") (pinfunction "VBUS_B4A9") (pintype "power_in"))
      (node (ref "TVS1") (pin "5") (pinfunction "VCC_5") (pintype "power_in"))
    )
    (net (code "79") (name "unconnected-(B1-*D3-PadD3)") (class "Default")
      (node (ref "B1") (pin "D3") (pinfunction "*D3_D3") (pintype "bidirectional"))
    )
    (net (code "80") (name "unconnected-(B1-*D5-PadD5)") (class "Default")
      (node (ref "B1") (pin "D5") (pinfunction "*D5_D5") (pintype "bidirectional"))
    )
    (net (code "81") (name "unconnected-(B1-*D6-PadD6)") (class "Default")
      (node (ref "B1") (pin "D6") (pinfunction "*D6_D6") (pintype "bidirectional"))
    )
    (net (code "82") (name "unconnected-(B1-*D9-PadD9)") (class "Default")
      (node (ref "B1") (pin "D9") (pinfunction "*D9_D9") (pintype "bidirectional"))
    )
    (net (code "83") (name "unconnected-(B1-*D10-PadD10)") (class "Default")
      (node (ref "B1") (pin "D10") (pinfunction "*D10_D10") (pintype "bidirectional"))
    )
    (net (code "84") (name "unconnected-(B1-*D11-PadD11)") (class "Default")
      (node (ref "B1") (pin "D11") (pinfunction "*D11_D11") (pintype "bidirectional"))
    )
    (net (code "85") (name "unconnected-(B1-GND-PadGND@1)") (class "Default")
      (node (ref "B1") (pin "GND@1") (pinfunction "GND_GND@1") (pintype "bidirectional"))
    )
    (net (code "86") (name "unconnected-(B1-GND-PadGND@2)") (class "Default")
      (node (ref "B1") (pin "GND@2") (pinfunction "GND_GND@2") (pintype "bidirectional"))
    )
    (net (code "87") (name "unconnected-(B1-GND-PadGND@3)") (class "Default")
      (node (ref "B1") (pin "GND@3") (pinfunction "GND_GND@3") (pintype "bidirectional"))
    )
    (net (code "88") (name "unconnected-(B1-GND-PadGND@4)") (class "Default")
      (node (ref "B1") (pin "GND@4") (pinfunction "GND_GND@4") (pintype "bidirectional"))
    )
    (net (code "89") (name "unconnected-(B1-Pad3.3V)") (class "Default")
      (node (ref "B1") (pin "3.3V") (pinfunction "3.3V_3.3V") (pintype "bidirectional"))
    )
    (net (code "90") (name "unconnected-(B1-Pad5V)") (class "Default")
      (node (ref "B1") (pin "5V") (pinfunction "5V_5V") (pintype "bidirectional"))
    )
    (net (code "91") (name "unconnected-(B1-PadA0)") (class "Default")
      (node (ref "B1") (pin "A0") (pinfunction "A0_A0") (pintype "bidirectional"))
    )
    (net (code "92") (name "unconnected-(B1-PadA1)") (class "Default")
      (node (ref "B1") (pin "A1") (pinfunction "A1_A1") (pintype "bidirectional"))
    )
    (net (code "93") (name "unconnected-(B1-PadA2)") (class "Default")
      (node (ref "B1") (pin "A2") (pinfunction "A2_A2") (pintype "bidirectional"))
    )
    (net (code "94") (name "unconnected-(B1-PadA3)") (class "Default")
      (node (ref "B1") (pin "A3") (pinfunction "A3_A3") (pintype "bidirectional"))
    )
    (net (code "95") (name "unconnected-(B1-PadA4)") (class "Default")
      (node (ref "B1") (pin "A4") (pinfunction "A4_A4") (pintype "bidirectional"))
    )
    (net (code "96") (name "unconnected-(B1-PadA5)") (class "Default")
      (node (ref "B1") (pin "A5") (pinfunction "A5_A5") (pintype "bidirectional"))
    )
    (net (code "97") (name "unconnected-(B1-PadAREF)") (class "Default")
      (node (ref "B1") (pin "AREF") (pinfunction "AREF_AREF") (pintype "bidirectional"))
    )
    (net (code "98") (name "unconnected-(B1-PadD0)") (class "Default")
      (node (ref "B1") (pin "D0") (pinfunction "D0_D0") (pintype "bidirectional"))
    )
    (net (code "99") (name "unconnected-(B1-PadD1)") (class "Default")
      (node (ref "B1") (pin "D1") (pinfunction "D1_D1") (pintype "bidirectional"))
    )
    (net (code "100") (name "unconnected-(B1-PadD2)") (class "Default")
      (node (ref "B1") (pin "D2") (pinfunction "D2_D2") (pintype "bidirectional"))
    )
    (net (code "101") (name "unconnected-(B1-PadD4)") (class "Default")
      (node (ref "B1") (pin "D4") (pinfunction "D4_D4") (pintype "bidirectional"))
    )
    (net (code "102") (name "unconnected-(B1-PadD7)") (class "Default")
      (node (ref "B1") (pin "D7") (pinfunction "D7_D7") (pintype "bidirectional"))
    )
    (net (code "103") (name "unconnected-(B1-PadD8)") (class "Default")
      (node (ref "B1") (pin "D8") (pinfunction "D8_D8") (pintype "bidirectional"))
    )
    (net (code "104") (name "unconnected-(B1-PadD12)") (class "Default")
      (node (ref "B1") (pin "D12") (pinfunction "D12_D12") (pintype "bidirectional"))
    )
    (net (code "105") (name "unconnected-(B1-PadD13)") (class "Default")
      (node (ref "B1") (pin "D13") (pinfunction "D13_D13") (pintype "bidirectional"))
    )
    (net (code "106") (name "unconnected-(B1-PadIOREF)") (class "Default")
      (node (ref "B1") (pin "IOREF") (pinfunction "IOREF_IOREF") (pintype "bidirectional"))
    )
    (net (code "107") (name "unconnected-(B1-PadMISO)") (class "Default")
      (node (ref "B1") (pin "MISO") (pinfunction "MISO_MISO") (pintype "bidirectional"))
    )
    (net (code "108") (name "unconnected-(B1-PadMOSI)") (class "Default")
      (node (ref "B1") (pin "MOSI") (pinfunction "MOSI_MOSI") (pintype "bidirectional"))
    )
    (net (code "109") (name "unconnected-(B1-PadSCK)") (class "Default")
      (node (ref "B1") (pin "SCK") (pinfunction "SCK_SCK") (pintype "bidirectional"))
    )
    (net (code "110") (name "unconnected-(B1-PadSCL)") (class "Default")
      (node (ref "B1") (pin "SCL") (pinfunction "SCL_SCL") (pintype "bidirectional"))
    )
    (net (code "111") (name "unconnected-(B1-PadSDA)") (class "Default")
      (node (ref "B1") (pin "SDA") (pinfunction "SDA_SDA") (pintype "bidirectional"))
    )
    (net (code "112") (name "unconnected-(B1-PadVCC)") (class "Default")
      (node (ref "B1") (pin "VCC") (pinfunction "VCC_VCC") (pintype "bidirectional"))
    )
    (net (code "113") (name "unconnected-(B1-PadVIN)") (class "Default")
      (node (ref "B1") (pin "VIN") (pinfunction "VIN_VIN") (pintype "bidirectional"))
    )
    (net (code "114") (name "unconnected-(B1-~{RESET}-PadRESET@1)") (class "Default")
      (node (ref "B1") (pin "RESET@1") (pinfunction "~{RESET}_RESET@1") (pintype "bidirectional"))
    )
    (net (code "115") (name "unconnected-(B1-~{RESET}-PadRESET@2)") (class "Default")
      (node (ref "B1") (pin "RESET@2") (pinfunction "~{RESET}_RESET@2") (pintype "bidirectional"))
    )
    (net (code "116") (name "unconnected-(J4-Pad1)") (class "Default")
      (node (ref "J4") (pin "1") (pinfunction "1_1") (pintype "passive"))
    )
    (net (code "117") (name "unconnected-(J4-Pad2)") (class "Default")
      (node (ref "J4") (pin "2") (pinfunction "2_2") (pintype "passive"))
    )
    (net (code "118") (name "unconnected-(J5-SBU1-PadA8)") (class "Default")
      (node (ref "J5") (pin "A8") (pinfunction "SBU1_A8") (pintype "bidirectional"))
    )
    (net (code "119") (name "unconnected-(J5-SBU2-PadB8)") (class "Default")
      (node (ref "J5") (pin "B8") (pinfunction "SBU2_B8") (pintype "bidirectional"))
    )
    (net (code "120") (name "unconnected-(R5B-1-Pad2)") (class "Default")
      (node (ref "R5") (pin "2") (pinfunction "1_2") (pintype "passive"))
    )
    (net (code "121") (name "unconnected-(R5B-2-Pad7)") (class "Default")
      (node (ref "R5") (pin "7") (pinfunction "2_7") (pintype "passive"))
    )
    (net (code "122") (name "unconnected-(R11-Pad1)") (class "Default")
      (node (ref "R11") (pin "1") (pinfunction "1_1") (pintype "passive"))
    )
    (net (code "123") (name "unconnected-(R11-Pad2)") (class "Default")
      (node (ref "R11") (pin "2") (pinfunction "2_2") (pintype "passive"))
    )
    (net (code "124") (name "unconnected-(TVS1-IO3-Pad4)") (class "Default")
      (node (ref "TVS1") (pin "4") (pinfunction "IO3_4") (pintype "passive"))
    )
    (net (code "125") (name "unconnected-(TVS1-IO4-Pad6)") (class "Default")
      (node (ref "TVS1") (pin "6") (pinfunction "IO4_6") (pintype "passive"))
    )
    (net (code "126") (name "unconnected-(U1-CLK-Pad20)") (class "Default")
      (node (ref "U1") (pin "20") (pinfunction "CLK_20") (pintype "bidirectional"))
    )
    (net (code "127") (name "unconnected-(U1-CMD-Pad19)") (class "Default")
      (node (ref "U1") (pin "19") (pinfunction "CMD_19") (pintype "bidirectional"))
    )
    (net (code "128") (name "unconnected-(U1-IO2-Pad24)") (class "Default")
      (node (ref "U1") (pin "24") (pinfunction "IO2_24") (pintype "bidirectional"))
    )
    (net (code "129") (name "unconnected-(U1-IO4-Pad26)") (class "Default")
      (node (ref "U1") (pin "26") (pinfunction "IO4_26") (pintype "bidirectional"))
    )
    (net (code "130") (name "unconnected-(U1-IO12-Pad14)") (class "Default")
      (node (ref "U1") (pin "14") (pinfunction "IO12_14") (pintype "bidirectional"))
    )
    (net (code "131") (name "unconnected-(U1-IO13-Pad16)") (class "Default")
      (node (ref "U1") (pin "16") (pinfunction "IO13_16") (pintype "bidirectional"))
    )
    (net (code "132") (name "unconnected-(U1-IO15-Pad23)") (class "Default")
      (node (ref "U1") (pin "23") (pinfunction "IO15_23") (pintype "bidirectional"))
    )
    (net (code "133") (name "unconnected-(U1-IO16-Pad27)") (class "Default")
      (node (ref "U1") (pin "27") (pinfunction "IO16_27") (pintype "bidirectional"))
    )
    (net (code "134") (name "unconnected-(U1-IO17-Pad28)") (class "Default")
      (node (ref "U1") (pin "28") (pinfunction "IO17_28") (pintype "bidirectional"))
    )
    (net (code "135") (name "unconnected-(U1-IO19-Pad31)") (class "Default")
      (node (ref "U1") (pin "31") (pinfunction "IO19_31") (pintype "bidirectional"))
    )
    (net (code "136") (name "unconnected-(U1-IO32-Pad8)") (class "Default")
      (node (ref "U1") (pin "8") (pinfunction "IO32_8") (pintype "bidirectional"))
    )
    (net (code "137") (name "unconnected-(U1-IO34-Pad6)") (class "Default")
      (node (ref "U1") (pin "6") (pinfunction "IO34_6") (pintype "bidirectional"))
    )
    (net (code "138") (name "unconnected-(U1-IO35-Pad7)") (class "Default")
      (node (ref "U1") (pin "7") (pinfunction "IO35_7") (pintype "bidirectional"))
    )
    (net (code "139") (name "unconnected-(U1-SD0-Pad21)") (class "Default")
      (node (ref "U1") (pin "21") (pinfunction "SD0_21") (pintype "bidirectional"))
    )
    (net (code "140") (name "unconnected-(U1-SD1-Pad22)") (class "Default")
      (node (ref "U1") (pin "22") (pinfunction "SD1_22") (pintype "bidirectional"))
    )
    (net (code "141") (name "unconnected-(U1-SD2-Pad17)") (class "Default")
      (node (ref "U1") (pin "17") (pinfunction "SD2_17") (pintype "bidirectional"))
    )
    (net (code "142") (name "unconnected-(U1-SD3-Pad18)") (class "Default")
      (node (ref "U1") (pin "18") (pinfunction "SD3_18") (pintype "bidirectional"))
    )
    (net (code "143") (name "unconnected-(U1-SVN-Pad5)") (class "Default")
      (node (ref "U1") (pin "5") (pinfunction "SVN_5") (pintype "bidirectional"))
    )
    (net (code "144") (name "unconnected-(U1-SVP-Pad4)") (class "Default")
      (node (ref "U1") (pin "4") (pinfunction "SVP_4") (pintype "bidirectional"))
    )
    (net (code "145") (name "unconnected-(U4-PA02-Pad18)") (class "Default")
      (node (ref "U4") (pin "18") (pinfunction "PA02_18") (pintype "bidirectional"))
    )
    (net (code "146") (name "unconnected-(U4-PA03-Pad19)") (class "Default")
      (node (ref "U4") (pin "19") (pinfunction "PA03_19") (pintype "bidirectional"))
    )
    (net (code "147") (name "unconnected-(U4-PA04-Pad20)") (class "Default")
      (node (ref "U4") (pin "20") (pinfunction "PA04_20") (pintype "bidirectional"))
    )
    (net (code "148") (name "unconnected-(U4-PA05-Pad1)") (class "Default")
      (node (ref "U4") (pin "1") (pinfunction "PA05_1") (pintype "bidirectional"))
    )
    (net (code "149") (name "unconnected-(U4-PA06-Pad2)") (class "Default")
      (node (ref "U4") (pin "2") (pinfunction "PA06_2") (pintype "bidirectional"))
    )
    (net (code "150") (name "unconnected-(U4-PA07-Pad3)") (class "Default")
      (node (ref "U4") (pin "3") (pinfunction "PA07_3") (pintype "bidirectional"))
    )
    (net (code "151") (name "unconnected-(U4-PA08{slash}XIN32-Pad4)") (class "Default")
      (node (ref "U4") (pin "4") (pinfunction "PA08/XIN32_4") (pintype "input"))
    )
    (net (code "152") (name "unconnected-(U4-PA09{slash}XOUT32-Pad5)") (class "Default")
      (node (ref "U4") (pin "5") (pinfunction "PA09/XOUT32_5") (pintype "input"))
    )
    (net (code "153") (name "unconnected-(U4-PA16-Pad8)") (class "Default")
      (node (ref "U4") (pin "8") (pinfunction "PA16_8") (pintype "bidirectional"))
    )
    (net (code "154") (name "unconnected-(U6-1A-Pad3)") (class "Default")
      (node (ref "U6") (pin "3") (pinfunction "1A_3") (pintype "bidirectional"))
    )
    (net (code "155") (name "unconnected-(U6-1Y-Pad2)") (class "Default")
      (node (ref "U6") (pin "2") (pinfunction "1Y_2") (pintype "bidirectional"))
    )
  )
)
